# schematic.net
KiCad netlist of a schematic drawn in EAGLE
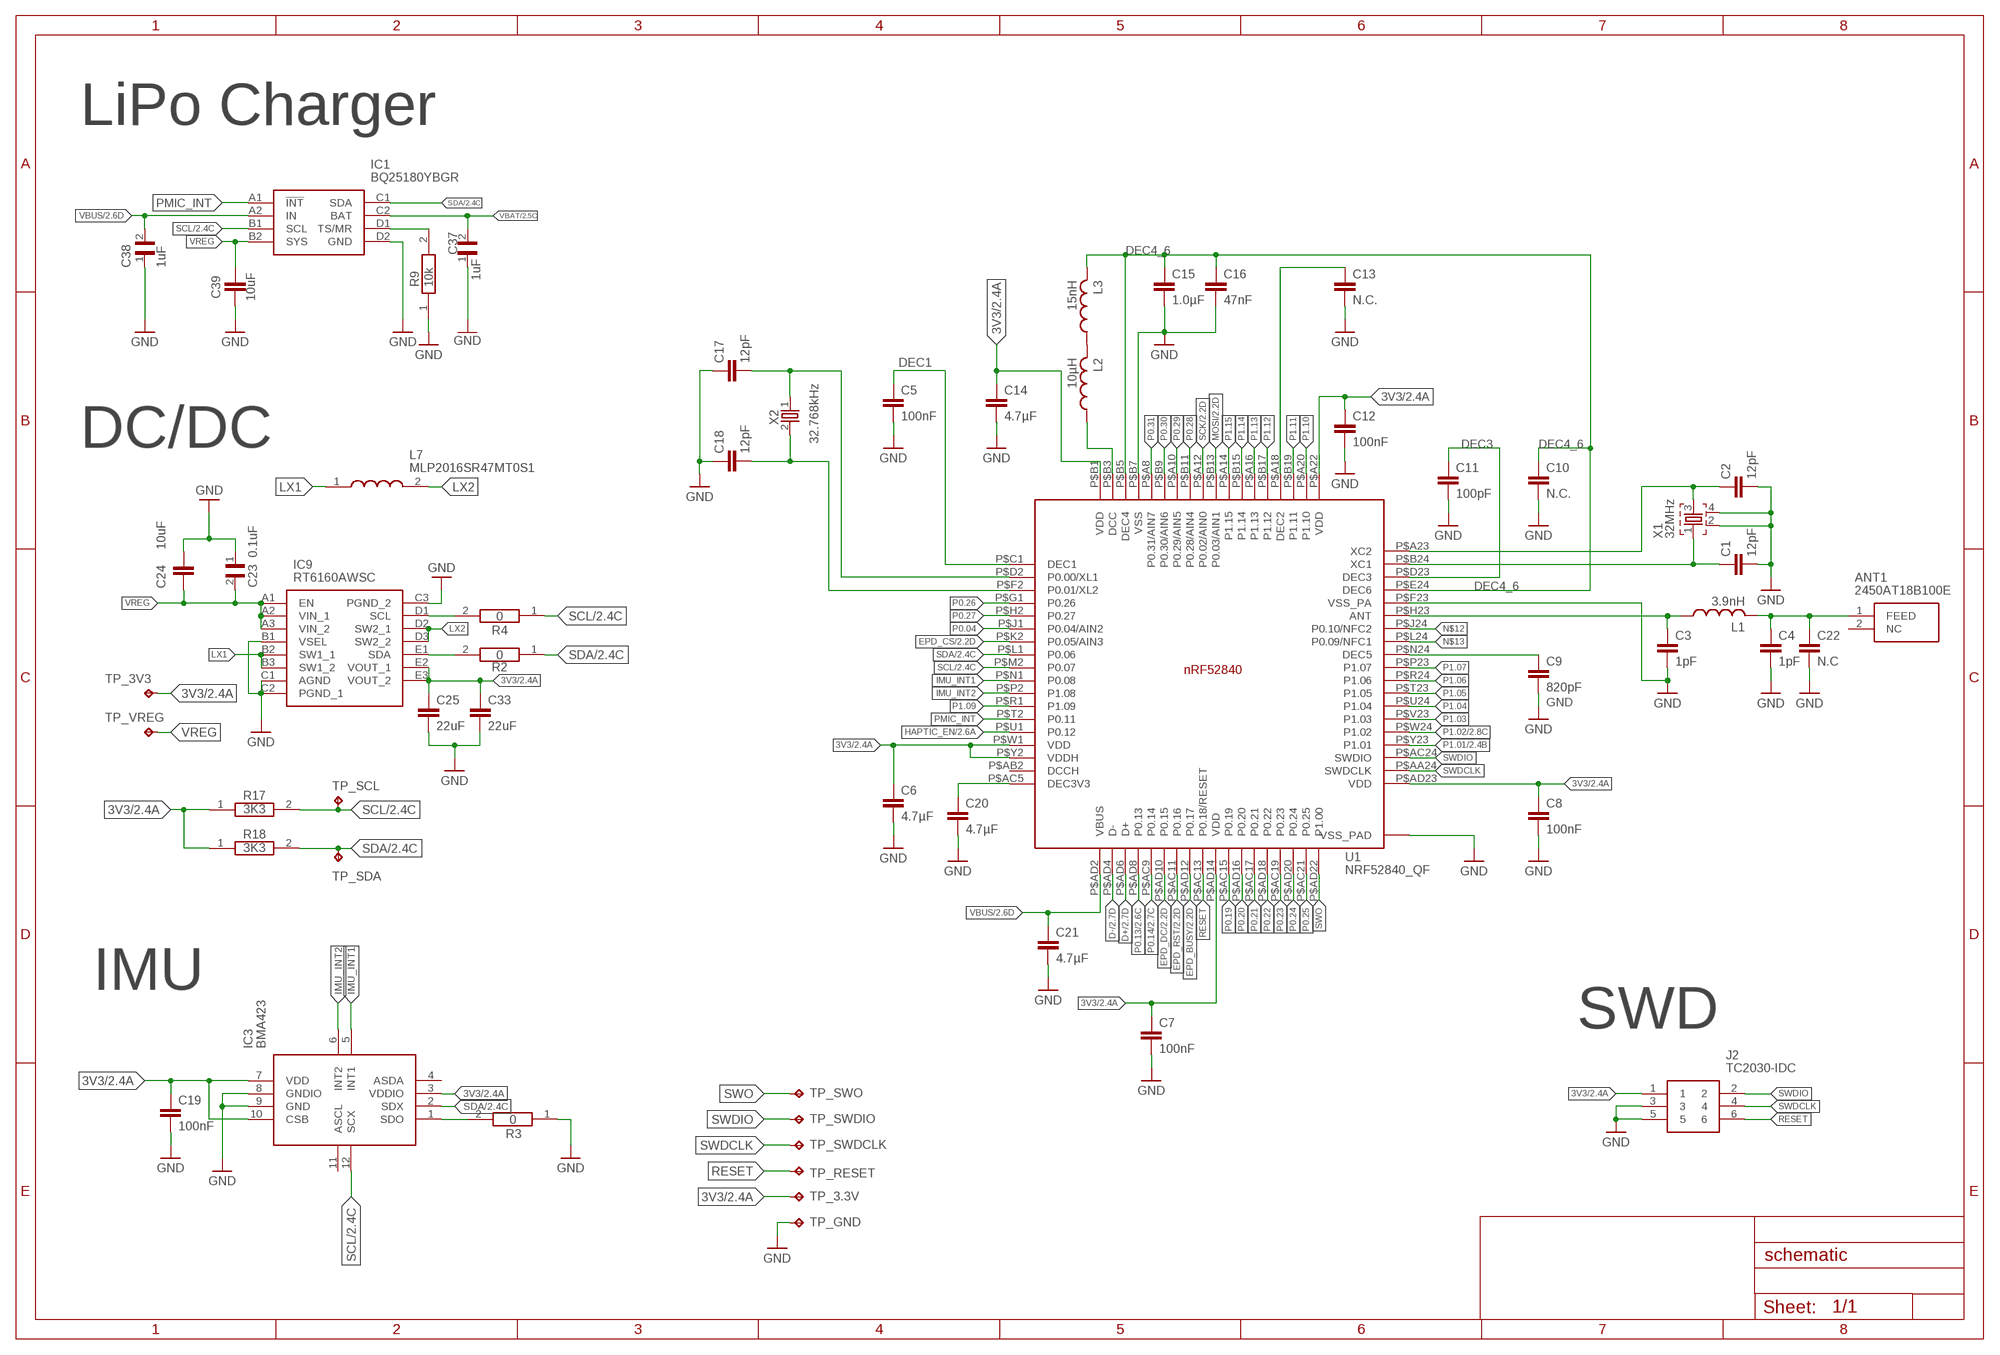
[diagram p0: schematic, sheet 1, part 1 of 2]
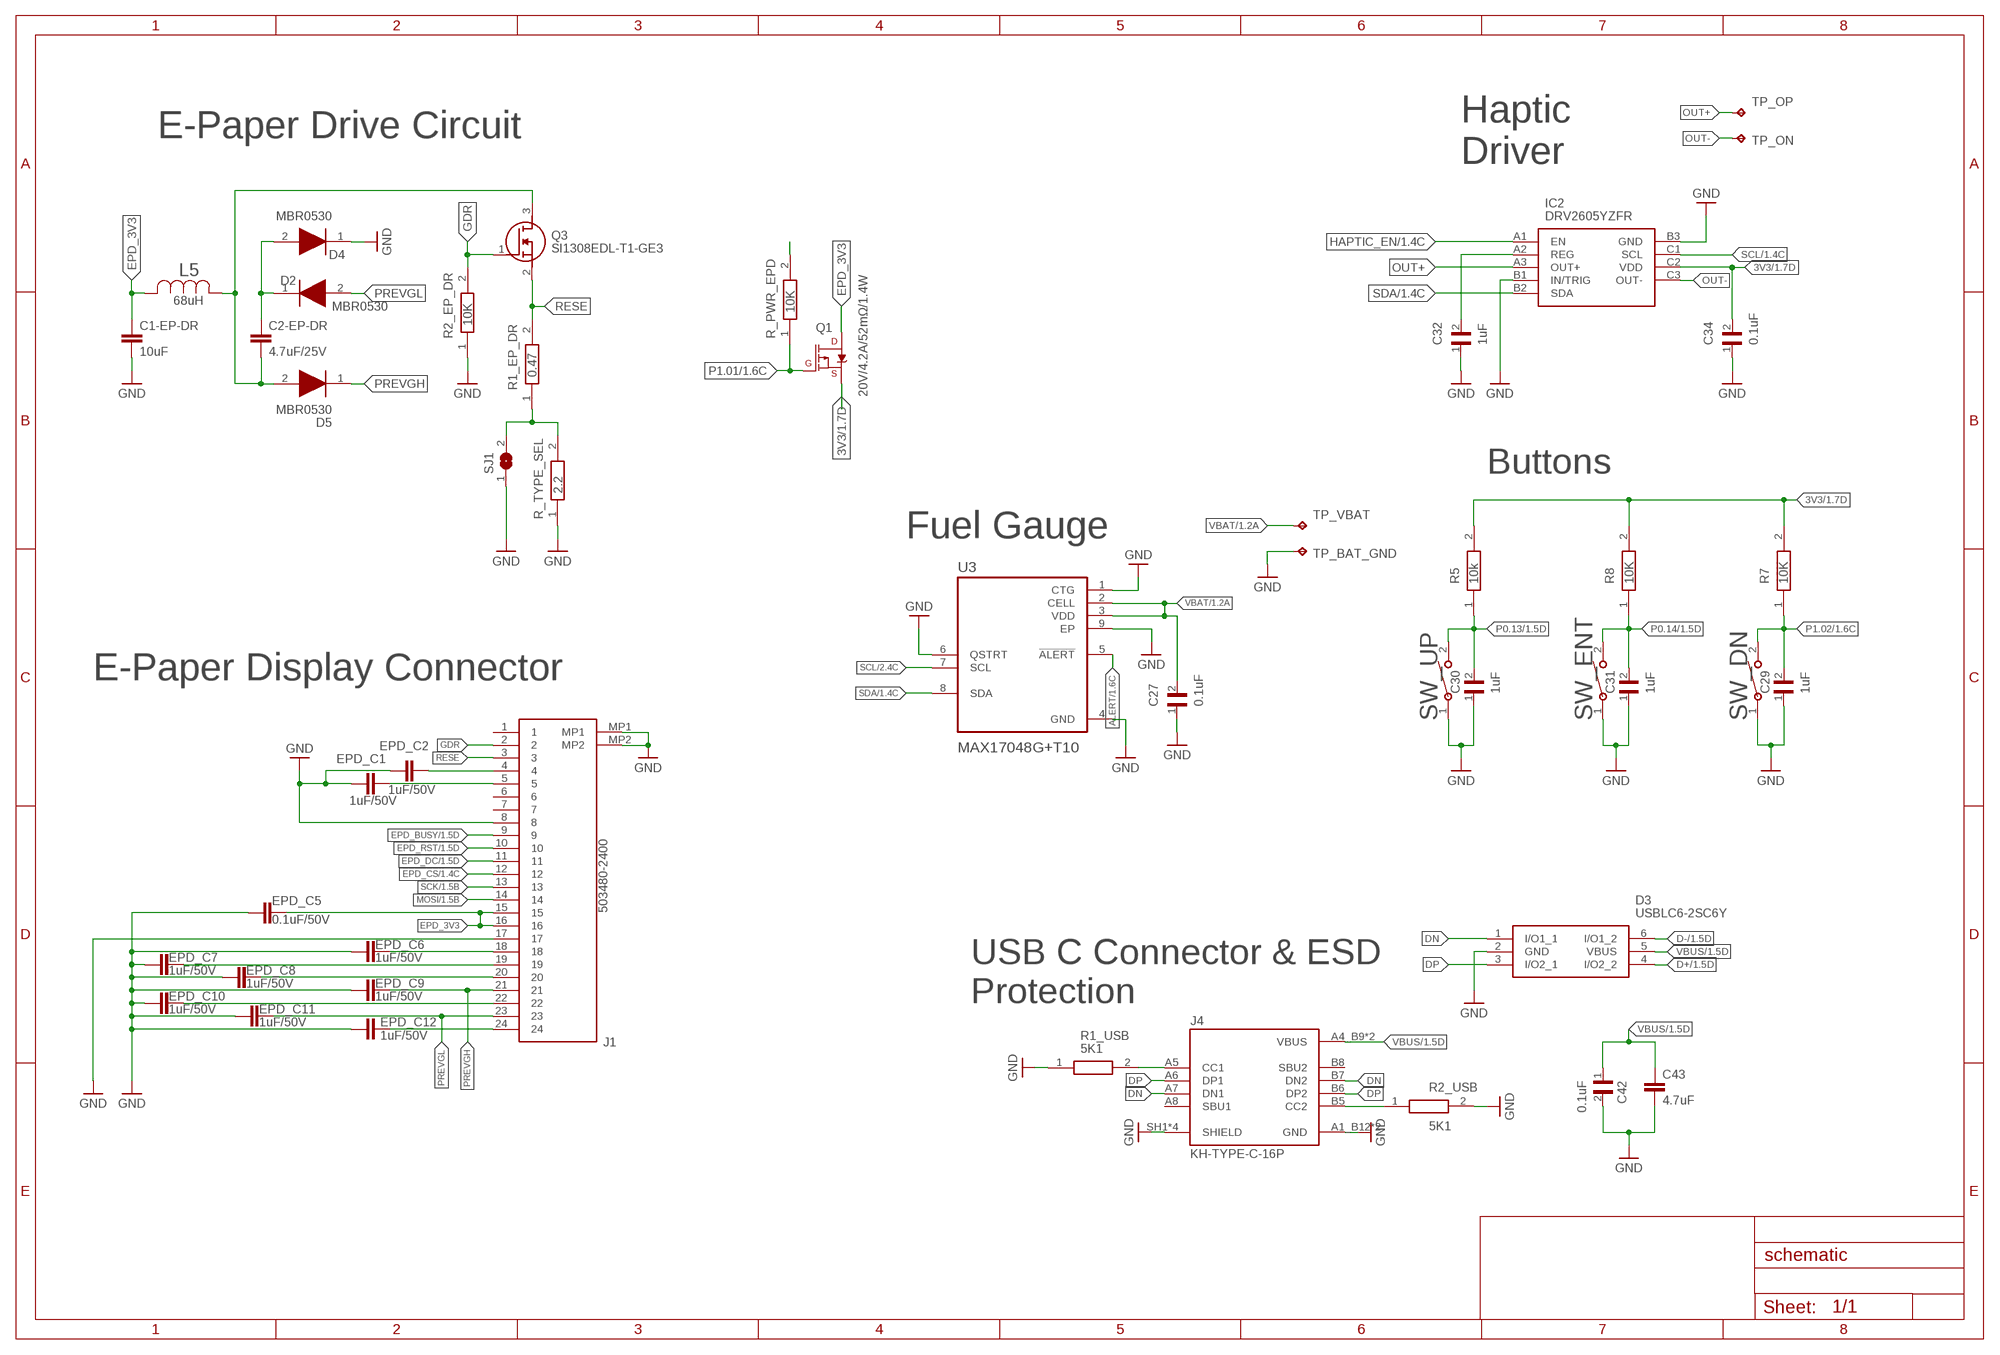
[diagram p1: schematic, sheet 1, part 2 of 2]

(export (version "E")
  (design (tool "Eeschema 10.0.6"))
  (components
    (comp (ref "ANT1")
      (value "2450AT18B100E")
      (footprint "eagle-import:2450AT18B100E_ANTC3216X140N")
      (fields (field (name "MOUSER_PART_NUMBER") "609-2450AT18B100E"))
      (libsource (lib "eagle-import") (part "2450AT18B100E_2450AT18B100E"))
    )
    (comp (ref "C1")
      (value "12pF")
      (footprint "eagle-import:NORDIC_NRF_3_RESC0201_L")
      (libsource (lib "eagle-import") (part "NORDIC_NRF_3_CAPACITOR_0201_L"))
    )
    (comp (ref "C1-EP-DR")
      (value "10uF")
      (footprint "eagle-import:PERFECT_0402_0402")
      (libsource (lib "eagle-import") (part "PERFECT_0402_CAP_0402"))
    )
    (comp (ref "C2")
      (value "12pF")
      (footprint "eagle-import:NORDIC_NRF_3_RESC0201_L")
      (libsource (lib "eagle-import") (part "NORDIC_NRF_3_CAPACITOR_0201_L"))
    )
    (comp (ref "C2-EP-DR")
      (value "4.7uF/25V")
      (footprint "eagle-import:PERFECT_0402_0402")
      (libsource (lib "eagle-import") (part "PERFECT_0402_CAP_0402"))
    )
    (comp (ref "C3")
      (value "1pF")
      (footprint "eagle-import:NORDIC_NRF_3_RESC0201_L")
      (libsource (lib "eagle-import") (part "NORDIC_NRF_3_CAPACITOR_0201_L"))
    )
    (comp (ref "C4")
      (value "1pF")
      (footprint "eagle-import:NORDIC_NRF_3_RESC0201_L")
      (libsource (lib "eagle-import") (part "NORDIC_NRF_3_CAPACITOR_0201_L"))
    )
    (comp (ref "C5")
      (value "100nF")
      (footprint "eagle-import:NORDIC_NRF_3_RESC0201_L")
      (libsource (lib "eagle-import") (part "NORDIC_NRF_3_CAPACITOR_0201_L"))
    )
    (comp (ref "C6")
      (value "4.7µF")
      (footprint "eagle-import:PERFECT_0402_0402")
      (libsource (lib "eagle-import") (part "PERFECT_0402_CAP_0402"))
    )
    (comp (ref "C7")
      (value "100nF")
      (footprint "eagle-import:NORDIC_NRF_3_RESC0201_L")
      (libsource (lib "eagle-import") (part "NORDIC_NRF_3_CAPACITOR_0201_L"))
    )
    (comp (ref "C8")
      (value "100nF")
      (footprint "eagle-import:NORDIC_NRF_3_RESC0201_L")
      (libsource (lib "eagle-import") (part "NORDIC_NRF_3_CAPACITOR_0201_L"))
    )
    (comp (ref "C9")
      (value "820pF")
      (footprint "eagle-import:NORDIC_NRF_3_RESC0201_L")
      (libsource (lib "eagle-import") (part "NORDIC_NRF_3_CAPACITOR_0201_L"))
    )
    (comp (ref "C10")
      (value "N.C.")
      (footprint "eagle-import:NORDIC_NRF_3_RESC0201_L")
      (libsource (lib "eagle-import") (part "NORDIC_NRF_3_CAPACITOR_0201_L"))
    )
    (comp (ref "C11")
      (value "100pF")
      (footprint "eagle-import:NORDIC_NRF_3_RESC0201_L")
      (libsource (lib "eagle-import") (part "NORDIC_NRF_3_CAPACITOR_0201_L"))
    )
    (comp (ref "C12")
      (value "100nF")
      (footprint "eagle-import:NORDIC_NRF_3_RESC0201_L")
      (libsource (lib "eagle-import") (part "NORDIC_NRF_3_CAPACITOR_0201_L"))
    )
    (comp (ref "C13")
      (value "N.C.")
      (footprint "eagle-import:NORDIC_NRF_3_RESC0201_L")
      (libsource (lib "eagle-import") (part "NORDIC_NRF_3_CAPACITOR_0201_L"))
    )
    (comp (ref "C14")
      (value "4.7µF")
      (footprint "eagle-import:PERFECT_0402_0402")
      (libsource (lib "eagle-import") (part "PERFECT_0402_CAP_0402"))
    )
    (comp (ref "C15")
      (value "1.0µF")
      (footprint "eagle-import:PERFECT_0402_0402")
      (libsource (lib "eagle-import") (part "PERFECT_0402_CAP_0402"))
    )
    (comp (ref "C16")
      (value "47nF")
      (footprint "eagle-import:NORDIC_NRF_3_RESC0201_L")
      (libsource (lib "eagle-import") (part "NORDIC_NRF_3_CAPACITOR_0201_L"))
    )
    (comp (ref "C17")
      (value "12pF")
      (footprint "eagle-import:NORDIC_NRF_3_RESC0201_L")
      (libsource (lib "eagle-import") (part "NORDIC_NRF_3_CAPACITOR_0201_L"))
    )
    (comp (ref "C18")
      (value "12pF")
      (footprint "eagle-import:NORDIC_NRF_3_RESC0201_L")
      (libsource (lib "eagle-import") (part "NORDIC_NRF_3_CAPACITOR_0201_L"))
    )
    (comp (ref "C19")
      (value "100nF")
      (footprint "eagle-import:NORDIC_NRF_3_RESC0201_L")
      (libsource (lib "eagle-import") (part "NORDIC_NRF_3_CAPACITOR_0201_L"))
    )
    (comp (ref "C20")
      (value "4.7µF")
      (footprint "eagle-import:PERFECT_0402_0402")
      (libsource (lib "eagle-import") (part "PERFECT_0402_CAP_0402"))
    )
    (comp (ref "C21")
      (value "4.7µF")
      (footprint "eagle-import:PERFECT_0402_0402")
      (libsource (lib "eagle-import") (part "PERFECT_0402_CAP_0402"))
    )
    (comp (ref "C22")
      (value "N.C")
      (footprint "eagle-import:NORDIC_NRF_3_RESC0201_L")
      (libsource (lib "eagle-import") (part "NORDIC_NRF_3_CAPACITOR_0201_L"))
    )
    (comp (ref "C23")
      (value "0.1uF")
      (footprint "eagle-import:ERA-1AEB3401C_0201")
      (libsource (lib "eagle-import") (part "GRM011R60J152KE01L_1_GRM011R60J152KE01L"))
    )
    (comp (ref "C24")
      (value "10uF")
      (footprint "eagle-import:PERFECT_0402_0402")
      (libsource (lib "eagle-import") (part "PERFECT_0402_CAP_0402"))
    )
    (comp (ref "C25")
      (value "22uF")
      (footprint "eagle-import:PERFECT_0402_0402")
      (libsource (lib "eagle-import") (part "PERFECT_0402_CAP_0402"))
    )
    (comp (ref "C27")
      (value "0.1uF")
      (footprint "eagle-import:ERA-1AEB3401C_0201")
      (libsource (lib "eagle-import") (part "GRM011R60J152KE01L_1_GRM011R60J152KE01L"))
    )
    (comp (ref "C29")
      (value "1uF")
      (footprint "eagle-import:ERA-1AEB3401C_0201")
      (libsource (lib "eagle-import") (part "GRM011R60J152KE01L_1_GRM011R60J152KE01L"))
    )
    (comp (ref "C30")
      (value "1uF")
      (footprint "eagle-import:ERA-1AEB3401C_0201")
      (libsource (lib "eagle-import") (part "GRM011R60J152KE01L_1_GRM011R60J152KE01L"))
    )
    (comp (ref "C31")
      (value "1uF")
      (footprint "eagle-import:ERA-1AEB3401C_0201")
      (libsource (lib "eagle-import") (part "GRM011R60J152KE01L_1_GRM011R60J152KE01L"))
    )
    (comp (ref "C32")
      (value "1uF")
      (footprint "eagle-import:ERA-1AEB3401C_0201")
      (libsource (lib "eagle-import") (part "GRM011R60J152KE01L_1_GRM011R60J152KE01L"))
    )
    (comp (ref "C33")
      (value "22uF")
      (footprint "eagle-import:PERFECT_0402_0402")
      (libsource (lib "eagle-import") (part "PERFECT_0402_CAP_0402"))
    )
    (comp (ref "C34")
      (value "0.1uF")
      (footprint "eagle-import:ERA-1AEB3401C_0201")
      (libsource (lib "eagle-import") (part "GRM011R60J152KE01L_1_GRM011R60J152KE01L"))
    )
    (comp (ref "C37")
      (value "1uF")
      (footprint "eagle-import:ERA-1AEB3401C_0201")
      (libsource (lib "eagle-import") (part "GRM011R60J152KE01L_1_GRM011R60J152KE01L"))
    )
    (comp (ref "C38")
      (value "1uF")
      (footprint "eagle-import:ERA-1AEB3401C_0201")
      (libsource (lib "eagle-import") (part "GRM011R60J152KE01L_1_GRM011R60J152KE01L"))
    )
    (comp (ref "C39")
      (value "10uF")
      (footprint "eagle-import:PERFECT_0402_0402")
      (libsource (lib "eagle-import") (part "PERFECT_0402_CAP_0402"))
    )
    (comp (ref "C42")
      (value "0.1uF")
      (footprint "eagle-import:ERA-1AEB3401C_0201")
      (libsource (lib "eagle-import") (part "GRM011R60J152KE01L_1_GRM011R60J152KE01L"))
    )
    (comp (ref "C43")
      (value "4.7uF")
      (footprint "eagle-import:PERFECT_0402_0402")
      (libsource (lib "eagle-import") (part "PERFECT_0402_CAP_0402"))
    )
    (comp (ref "D2")
      (value "MBR0530")
      (footprint "eagle-import:ESP32_C6_LIBRARY_5_SOD3716X135N")
      (fields (field (name "MF") "ON Semiconductor"))
      (libsource (lib "eagle-import") (part "ESP32_C6_LIBRARY_5_MBR0530"))
    )
    (comp (ref "D3")
      (value "USBLC6-2SC6Y")
      (footprint "eagle-import:ESP32_C6_LIBRARY_3_SOT95P280X145-6N")
      (fields (field (name "MF") "STMicroelectronics"))
      (libsource (lib "eagle-import") (part "ESP32_C6_LIBRARY_3_USBLC6-2SC6Y"))
    )
    (comp (ref "D4")
      (value "MBR0530")
      (footprint "eagle-import:ESP32_C6_LIBRARY_5_SOD3716X135N")
      (fields (field (name "MF") "ON Semiconductor"))
      (libsource (lib "eagle-import") (part "ESP32_C6_LIBRARY_5_MBR0530"))
    )
    (comp (ref "D5")
      (value "MBR0530")
      (footprint "eagle-import:ESP32_C6_LIBRARY_5_SOD3716X135N")
      (fields (field (name "MF") "ON Semiconductor"))
      (libsource (lib "eagle-import") (part "ESP32_C6_LIBRARY_5_MBR0530"))
    )
    (comp (ref "EPD_C1")
      (value "1uF/50V")
      (footprint "eagle-import:PERFECT_0402_0402")
      (libsource (lib "eagle-import") (part "PERFECT_0402_CAP_0402"))
    )
    (comp (ref "EPD_C2")
      (value "1uF/50V")
      (footprint "eagle-import:PERFECT_0402_0402")
      (libsource (lib "eagle-import") (part "PERFECT_0402_CAP_0402"))
    )
    (comp (ref "EPD_C5")
      (value "0.1uF/50V")
      (footprint "eagle-import:NORDIC_NRF_3_RESC0201_L")
      (libsource (lib "eagle-import") (part "NORDIC_NRF_3_CAPACITOR_0201_L"))
    )
    (comp (ref "EPD_C6")
      (value "1uF/50V")
      (footprint "eagle-import:PERFECT_0402_0402")
      (libsource (lib "eagle-import") (part "PERFECT_0402_CAP_0402"))
    )
    (comp (ref "EPD_C7")
      (value "1uF/50V")
      (footprint "eagle-import:PERFECT_0402_0402")
      (libsource (lib "eagle-import") (part "PERFECT_0402_CAP_0402"))
    )
    (comp (ref "EPD_C8")
      (value "1uF/50V")
      (footprint "eagle-import:PERFECT_0402_0402")
      (libsource (lib "eagle-import") (part "PERFECT_0402_CAP_0402"))
    )
    (comp (ref "EPD_C9")
      (value "1uF/50V")
      (footprint "eagle-import:PERFECT_0402_0402")
      (libsource (lib "eagle-import") (part "PERFECT_0402_CAP_0402"))
    )
    (comp (ref "EPD_C10")
      (value "1uF/50V")
      (footprint "eagle-import:PERFECT_0402_0402")
      (libsource (lib "eagle-import") (part "PERFECT_0402_CAP_0402"))
    )
    (comp (ref "EPD_C11")
      (value "1uF/50V")
      (footprint "eagle-import:PERFECT_0402_0402")
      (libsource (lib "eagle-import") (part "PERFECT_0402_CAP_0402"))
    )
    (comp (ref "EPD_C12")
      (value "1uF/50V")
      (footprint "eagle-import:PERFECT_0402_0402")
      (libsource (lib "eagle-import") (part "PERFECT_0402_CAP_0402"))
    )
    (comp (ref "IC1")
      (value "BQ25180YBGR")
      (footprint "eagle-import:BQ25180YBGR_BGA8C40P2X4_100X155X50")
      (fields (field (name "MOUSER_PART_NUMBER") "595-BQ25180YBGR"))
      (libsource (lib "eagle-import") (part "BQ25180YBGR_BQ25180YBGR"))
    )
    (comp (ref "IC2")
      (value "DRV2605YZFR")
      (footprint "eagle-import:DRV2605YZFR_BGA9C50P3X3_144X144X62")
      (libsource (lib "eagle-import") (part "DRV2605YZFR_DRV2605YZFR"))
    )
    (comp (ref "IC3")
      (value "BMA423")
      (footprint "eagle-import:BMA423_BMA423")
      (fields (field (name "MOUSER_PART_NUMBER") "262-BMA423"))
      (libsource (lib "eagle-import") (part "BMA423_BMA423"))
    )
    (comp (ref "IC9")
      (value "RT6160AWSC")
      (footprint "eagle-import:RT6160AWSC_BGA15C40P3X5_140X230X60")
      (fields (field (name "MOUSER_PART_NUMBER") "835-RT6160AWSC"))
      (libsource (lib "eagle-import") (part "RT6160AWSC_RT6160AWSC"))
    )
    (comp (ref "J1")
      (value "503480-2400")
      (footprint "eagle-import:503480-2400_5034802400")
      (fields (field (name "MOUSER_PART_NUMBER") "538-503480-2400"))
      (libsource (lib "eagle-import") (part "503480-2400_503480-2400"))
    )
    (comp (ref "J2")
      (value "TC2030-IDC")
      (footprint "eagle-import:TC2030-IDC_TC2030IDC")
      (libsource (lib "eagle-import") (part "TC2030-IDC_TC2030-IDC"))
    )
    (comp (ref "J4")
      (value "KH-TYPE-C-16P")
      (footprint "eagle-import:KH-TYPE-C-16P_KINGHELM_KH-TYPE-C-16P")
      (fields (field (name "MF") "kinghelm"))
      (libsource (lib "eagle-import") (part "KH-TYPE-C-16P_KH-TYPE-C-16P"))
    )
    (comp (ref "L1")
      (value "3.9nH")
      (footprint "eagle-import:NORDIC_NRF_2_RESC0402_N")
      (libsource (lib "eagle-import") (part "NORDIC_NRF_2_INDUCTOR_0402_L"))
    )
    (comp (ref "L2")
      (value "10µH")
      (footprint "eagle-import:NORDIC_NRF_2_RESC0402_N")
      (libsource (lib "eagle-import") (part "NORDIC_NRF_2_INDUCTOR_0402_L"))
    )
    (comp (ref "L3")
      (value "15nH")
      (footprint "eagle-import:NORDIC_NRF_2_RESC0402_N")
      (libsource (lib "eagle-import") (part "NORDIC_NRF_2_INDUCTOR_0402_L"))
    )
    (comp (ref "L5")
      (value "68uH")
      (footprint "eagle-import:ESP32_C6_LIBRARY_2_IND_4828-WE-TPC_WRE")
      (fields
        (field (name "MANUFACTURER_PART_NUMBER") "744043680")
        (field (name "COPYRIGHT") "Copyright (C) 2024 Ultra Librarian. All rights reserved.")
      )
      (libsource (lib "eagle-import") (part "ESP32_C6_LIBRARY_2_744043680IND_4828-WE-TPC_WRE"))
    )
    (comp (ref "L7")
      (value "MLP2016SR47MT0S1")
      (footprint "eagle-import:MLP2016SR47MT0S1_INDC2016X100N")
      (fields (field (name "MANUFACTURER_PART_NUMBER") "FTC252012SR47MBCA"))
      (libsource (lib "eagle-import") (part "MLP2016SR47MT0S1_FTC252012SR47MBCA"))
    )
    (comp (ref "Q1")
      (value "20V/4.2A/52mΩ/1.4W")
      (footprint "eagle-import:ESP32_C6_LIBRARY_4_ESP32_C6_LIBRARY_4_ESP32_C6_LIBRARY_4_ESP32_C6_LIBRARY_4_ESP32_WROVER_SPARKFUN-DISCRETESEMI_SOT23-3")
      (libsource (lib "eagle-import") (part "ESP32_C6_LIBRARY_4_ESP32_WROVER_SPARKFUN-DISCRETESEMI_MOSFET_PCH-DMG2305UX-7"))
    )
    (comp (ref "Q3")
      (value "SI1308EDL-T1-GE3")
      (footprint "eagle-import:ESP32_C6_LIBRARY_6_SOT65P210X110-3N")
      (fields (field (name "MF") "Vishay Siliconix"))
      (libsource (lib "eagle-import") (part "ESP32_C6_LIBRARY_6_SI1308EDL-T1-GE3"))
    )
    (comp (ref "R1_EP_DR")
      (value "0.47")
      (footprint "eagle-import:CPF0201D7K68C1_0201")
      (libsource (lib "eagle-import") (part "CPF0201D7K68C1_CPF0201D7K68C1"))
    )
    (comp (ref "R1_USB")
      (value "5K1")
      (footprint "eagle-import:CPF0201D7K68C1_0201")
      (libsource (lib "eagle-import") (part "CPF0201D7K68C1_CPF0201D7K68C1"))
    )
    (comp (ref "R2")
      (value "0")
      (footprint "eagle-import:ERA-1AEB3401C_0201")
      (libsource (lib "eagle-import") (part "ERA-1AEB3401C_CPF0201D7K68C1"))
    )
    (comp (ref "R2_EP_DR")
      (value "10K")
      (footprint "eagle-import:CPF0201D7K68C1_0201")
      (libsource (lib "eagle-import") (part "CPF0201D7K68C1_CPF0201D7K68C1"))
    )
    (comp (ref "R2_USB")
      (value "5K1")
      (footprint "eagle-import:CPF0201D7K68C1_0201")
      (libsource (lib "eagle-import") (part "CPF0201D7K68C1_CPF0201D7K68C1"))
    )
    (comp (ref "R3")
      (value "0")
      (footprint "eagle-import:CPF0201D7K68C1_0201")
      (libsource (lib "eagle-import") (part "CPF0201D7K68C1_CPF0201D7K68C1"))
    )
    (comp (ref "R4")
      (value "0")
      (footprint "eagle-import:ERA-1AEB3401C_0201")
      (libsource (lib "eagle-import") (part "ERA-1AEB3401C_CPF0201D7K68C1"))
    )
    (comp (ref "R5")
      (value "10k")
      (footprint "eagle-import:CPF0201D7K68C1_0201")
      (libsource (lib "eagle-import") (part "CPF0201D7K68C1_CPF0201D7K68C1"))
    )
    (comp (ref "R7")
      (value "10K")
      (footprint "eagle-import:CPF0201D7K68C1_0201")
      (libsource (lib "eagle-import") (part "CPF0201D7K68C1_CPF0201D7K68C1"))
    )
    (comp (ref "R8")
      (value "10K")
      (footprint "eagle-import:CPF0201D7K68C1_0201")
      (libsource (lib "eagle-import") (part "CPF0201D7K68C1_CPF0201D7K68C1"))
    )
    (comp (ref "R9")
      (value "10k")
      (footprint "eagle-import:ERA-1AEB3401C_0201")
      (libsource (lib "eagle-import") (part "ERA-1AEB3401C_CPF0201D7K68C1"))
    )
    (comp (ref "R17")
      (value "3K3")
      (footprint "eagle-import:ERA-1AEB3401C_0201")
      (libsource (lib "eagle-import") (part "ERA-1AEB3401C_CPF0201D7K68C1"))
    )
    (comp (ref "R18")
      (value "3K3")
      (footprint "eagle-import:ERA-1AEB3401C_0201")
      (libsource (lib "eagle-import") (part "ERA-1AEB3401C_CPF0201D7K68C1"))
    )
    (comp (ref "R_PWR_EPD")
      (value "10K")
      (footprint "eagle-import:CPF0201D7K68C1_0201")
      (libsource (lib "eagle-import") (part "CPF0201D7K68C1_CPF0201D7K68C1"))
    )
    (comp (ref "R_TYPE_SEL")
      (value "2.2")
      (footprint "eagle-import:CPF0201D7K68C1_0201")
      (libsource (lib "eagle-import") (part "CPF0201D7K68C1_CPF0201D7K68C1"))
    )
    (comp (ref "SJ1")
      (value "ESP32_C6_LIBRARY_7_JUMPER_SJ")
      (footprint "eagle-import:ESP32_C6_LIBRARY_7_JUMPER_SJ")
      (libsource (lib "eagle-import") (part "ESP32_C6_LIBRARY_7_JUMPER_SJ"))
    )
    (comp (ref "SW_DN")
      (value "2025-10-22_07-23-44_LIBRARY_EVP-AKE31ASW_EVP-AKE31A_PAN")
      (footprint "eagle-import:2025-10-22_07-23-44_LIBRARY_SW_EVP-AKE31A_PAN")
      (fields
        (field (name "MANUFACTURER_PART_NUMBER") "EVP-AKE31A")
        (field (name "COPYRIGHT") "Copyright (C) 2025 Ultra Librarian. All rights reserved.")
      )
      (libsource (lib "eagle-import") (part "2025-10-22_07-23-44_LIBRARY_EVP-AKE31ASW_EVP-AKE31A_PAN"))
    )
    (comp (ref "SW_ENT")
      (value "2025-10-22_07-23-44_LIBRARY_EVP-AKE31ASW_EVP-AKE31A_PAN")
      (footprint "eagle-import:2025-10-22_07-23-44_LIBRARY_SW_EVP-AKE31A_PAN")
      (fields
        (field (name "MANUFACTURER_PART_NUMBER") "EVP-AKE31A")
        (field (name "COPYRIGHT") "Copyright (C) 2025 Ultra Librarian. All rights reserved.")
      )
      (libsource (lib "eagle-import") (part "2025-10-22_07-23-44_LIBRARY_EVP-AKE31ASW_EVP-AKE31A_PAN"))
    )
    (comp (ref "SW_UP")
      (value "2025-10-22_07-23-44_LIBRARY_EVP-AKE31ASW_EVP-AKE31A_PAN")
      (footprint "eagle-import:2025-10-22_07-23-44_LIBRARY_SW_EVP-AKE31A_PAN")
      (fields
        (field (name "MANUFACTURER_PART_NUMBER") "EVP-AKE31A")
        (field (name "COPYRIGHT") "Copyright (C) 2025 Ultra Librarian. All rights reserved.")
      )
      (libsource (lib "eagle-import") (part "2025-10-22_07-23-44_LIBRARY_EVP-AKE31ASW_EVP-AKE31A_PAN"))
    )
    (comp (ref "TP_3.3V")
      (value "HECTOR_WATCH_1_TPTP20R")
      (footprint "eagle-import:HECTOR_WATCH_1_TP20R")
      (libsource (lib "eagle-import") (part "HECTOR_WATCH_1_TPTP20R"))
    )
    (comp (ref "TP_3V3")
      (value "HECTOR_WATCH_1_TPTP20R")
      (footprint "eagle-import:HECTOR_WATCH_1_TP20R")
      (libsource (lib "eagle-import") (part "HECTOR_WATCH_1_TPTP20R"))
    )
    (comp (ref "TP_BAT_GND")
      (value "HECTOR_WATCH_1_TPTP20R")
      (footprint "eagle-import:HECTOR_WATCH_1_TP20R")
      (libsource (lib "eagle-import") (part "HECTOR_WATCH_1_TPTP20R"))
    )
    (comp (ref "TP_GND")
      (value "HECTOR_WATCH_1_TPTP20R")
      (footprint "eagle-import:HECTOR_WATCH_1_TP20R")
      (libsource (lib "eagle-import") (part "HECTOR_WATCH_1_TPTP20R"))
    )
    (comp (ref "TP_ON")
      (value "HECTOR_WATCH_1_TPTP20R")
      (footprint "eagle-import:HECTOR_WATCH_1_TP20R")
      (libsource (lib "eagle-import") (part "HECTOR_WATCH_1_TPTP20R"))
    )
    (comp (ref "TP_OP")
      (value "HECTOR_WATCH_1_TPTP20R")
      (footprint "eagle-import:HECTOR_WATCH_1_TP20R")
      (libsource (lib "eagle-import") (part "HECTOR_WATCH_1_TPTP20R"))
    )
    (comp (ref "TP_RESET")
      (value "HECTOR_WATCH_1_TPTP20R")
      (footprint "eagle-import:HECTOR_WATCH_1_TP20R")
      (libsource (lib "eagle-import") (part "HECTOR_WATCH_1_TPTP20R"))
    )
    (comp (ref "TP_SCL")
      (value "HECTOR_WATCH_1_TPTP20R")
      (footprint "eagle-import:HECTOR_WATCH_1_TP20R")
      (libsource (lib "eagle-import") (part "HECTOR_WATCH_1_TPTP20R"))
    )
    (comp (ref "TP_SDA")
      (value "HECTOR_WATCH_1_TPTP20R")
      (footprint "eagle-import:HECTOR_WATCH_1_TP20R")
      (libsource (lib "eagle-import") (part "HECTOR_WATCH_1_TPTP20R"))
    )
    (comp (ref "TP_SWDCLK")
      (value "HECTOR_WATCH_1_TPTP20R")
      (footprint "eagle-import:HECTOR_WATCH_1_TP20R")
      (libsource (lib "eagle-import") (part "HECTOR_WATCH_1_TPTP20R"))
    )
    (comp (ref "TP_SWDIO")
      (value "HECTOR_WATCH_1_TPTP20R")
      (footprint "eagle-import:HECTOR_WATCH_1_TP20R")
      (libsource (lib "eagle-import") (part "HECTOR_WATCH_1_TPTP20R"))
    )
    (comp (ref "TP_SWO")
      (value "HECTOR_WATCH_1_TPTP20R")
      (footprint "eagle-import:HECTOR_WATCH_1_TP20R")
      (libsource (lib "eagle-import") (part "HECTOR_WATCH_1_TPTP20R"))
    )
    (comp (ref "TP_VBAT")
      (value "HECTOR_WATCH_1_TPTP20R")
      (footprint "eagle-import:HECTOR_WATCH_1_TP20R")
      (libsource (lib "eagle-import") (part "HECTOR_WATCH_1_TPTP20R"))
    )
    (comp (ref "TP_VREG")
      (value "HECTOR_WATCH_1_TPTP20R")
      (footprint "eagle-import:HECTOR_WATCH_1_TP20R")
      (libsource (lib "eagle-import") (part "HECTOR_WATCH_1_TPTP20R"))
    )
    (comp (ref "U1")
      (value "NRF52840_QF")
      (footprint "eagle-import:NORDIC_NRF_4_AQFN50P700X700X85_HS-74N")
      (libsource (lib "eagle-import") (part "NORDIC_NRF_4_NRF52840_QF"))
    )
    (comp (ref "U3")
      (value "MAX17048G+T10")
      (footprint "eagle-import:ESP32_C6_LIBRARY_SON50P200X200X80-9N")
      (fields (field (name "MF") "Analog Devices"))
      (libsource (lib "eagle-import") (part "ESP32_C6_LIBRARY_MAX17048G+T10"))
    )
    (comp (ref "X1")
      (value "32MHz")
      (footprint "eagle-import:NORDIC_NRF_BT-XTAL_2016_N")
      (libsource (lib "eagle-import") (part "NORDIC_NRF_XTAL_32MHZ"))
    )
    (comp (ref "X2")
      (value "32.768kHz")
      (footprint "eagle-import:NORDIC_NRF_1_XTAL_3215_N")
      (libsource (lib "eagle-import") (part "NORDIC_NRF_1_XTAL_32KHZ"))
    )
  )
  (nets
    (net (code "1") (name "/DEC1") (class "Default")
      (node (ref "C5") (pin "1") (pinfunction "1_1") (pintype "passive"))
      (node (ref "U1") (pin "P$C1") (pinfunction "DEC1_P$C1") (pintype "power_in"))
    )
    (net (code "2") (name "/DEC3") (class "Default")
      (node (ref "C11") (pin "1") (pinfunction "1_1") (pintype "passive"))
      (node (ref "U1") (pin "P$D23") (pinfunction "DEC3_P$D23") (pintype "bidirectional"))
    )
    (net (code "3") (name "/DEC4_6") (class "Default")
      (node (ref "C10") (pin "1") (pinfunction "1_1") (pintype "passive"))
      (node (ref "C15") (pin "1") (pinfunction "1_1") (pintype "passive"))
      (node (ref "C16") (pin "1") (pinfunction "1_1") (pintype "passive"))
      (node (ref "L3") (pin "2") (pinfunction "2_2") (pintype "passive"))
      (node (ref "U1") (pin "P$B5") (pinfunction "DEC4_P$B5") (pintype "power_in"))
      (node (ref "U1") (pin "P$E24") (pinfunction "DEC6_P$E24") (pintype "bidirectional"))
    )
    (net (code "4") (name "3V3{slash}1.7D") (class "Default")
      (node (ref "C34") (pin "2") (pinfunction "2_2") (pintype "passive"))
      (node (ref "IC2") (pin "C2") (pinfunction "VDD_C2") (pintype "bidirectional"))
      (node (ref "Q1") (pin "2") (pinfunction "S_2") (pintype "bidirectional"))
      (node (ref "R5") (pin "2") (pinfunction "2_2") (pintype "bidirectional"))
      (node (ref "R7") (pin "2") (pinfunction "2_2") (pintype "bidirectional"))
      (node (ref "R8") (pin "2") (pinfunction "2_2") (pintype "bidirectional"))
    )
    (net (code "5") (name "3V3{slash}2.4A") (class "Default")
      (node (ref "C12") (pin "1") (pinfunction "1_1") (pintype "passive"))
      (node (ref "C14") (pin "1") (pinfunction "1_1") (pintype "passive"))
      (node (ref "C19") (pin "1") (pinfunction "1_1") (pintype "passive"))
      (node (ref "C25") (pin "1") (pinfunction "1_1") (pintype "passive"))
      (node (ref "C33") (pin "1") (pinfunction "1_1") (pintype "passive"))
      (node (ref "C6") (pin "1") (pinfunction "1_1") (pintype "passive"))
      (node (ref "C7") (pin "1") (pinfunction "1_1") (pintype "passive"))
      (node (ref "C8") (pin "1") (pinfunction "1_1") (pintype "passive"))
      (node (ref "IC3") (pin "10") (pinfunction "CSB_10") (pintype "bidirectional"))
      (node (ref "IC3") (pin "3") (pinfunction "VDDIO_3") (pintype "bidirectional"))
      (node (ref "IC3") (pin "7") (pinfunction "VDD_7") (pintype "bidirectional"))
      (node (ref "IC9") (pin "E2") (pinfunction "VOUT_1_E2") (pintype "bidirectional"))
      (node (ref "IC9") (pin "E3") (pinfunction "VOUT_2_E3") (pintype "bidirectional"))
      (node (ref "J2") (pin "1") (pinfunction "1_1") (pintype "bidirectional"))
      (node (ref "R17") (pin "1") (pinfunction "1_1") (pintype "bidirectional"))
      (node (ref "R18") (pin "1") (pinfunction "1_1") (pintype "bidirectional"))
      (node (ref "TP_3.3V") (pin "TP") (pinfunction "TP_TP") (pintype "input"))
      (node (ref "TP_3V3") (pin "TP") (pinfunction "TP_TP") (pintype "input"))
      (node (ref "U1") (pin "P$A22") (pinfunction "VDD_P$A22") (pintype "power_in"))
      (node (ref "U1") (pin "P$AD14") (pinfunction "VDD_P$AD14") (pintype "power_in"))
      (node (ref "U1") (pin "P$AD23") (pinfunction "VDD_P$AD23") (pintype "power_in"))
      (node (ref "U1") (pin "P$B1") (pinfunction "VDD_P$B1") (pintype "power_in"))
      (node (ref "U1") (pin "P$W1") (pinfunction "VDD_P$W1") (pintype "power_in"))
      (node (ref "U1") (pin "P$Y2") (pinfunction "VDDH_P$Y2") (pintype "power_in"))
    )
    (net (code "6") (name "ALERT{slash}1.6C") (class "Default")
      (node (ref "U3") (pin "5") (pinfunction "~{ALERT}_5") (pintype "output"))
    )
    (net (code "7") (name "D+{slash}1.5D") (class "Default")
      (node (ref "D3") (pin "4") (pinfunction "I/O2_2_4") (pintype "bidirectional"))
    )
    (net (code "8") (name "D+{slash}2.7D") (class "Default")
      (node (ref "U1") (pin "P$AD6") (pinfunction "D+_P$AD6") (pintype "bidirectional"))
    )
    (net (code "9") (name "D-{slash}1.5D") (class "Default")
      (node (ref "D3") (pin "6") (pinfunction "I/O1_2_6") (pintype "bidirectional"))
    )
    (net (code "10") (name "D-{slash}2.7D") (class "Default")
      (node (ref "U1") (pin "P$AD4") (pinfunction "D-_P$AD4") (pintype "bidirectional"))
    )
    (net (code "11") (name "DN") (class "Default")
      (node (ref "D3") (pin "1") (pinfunction "I/O1_1_1") (pintype "bidirectional"))
      (node (ref "J4") (pin "A7") (pinfunction "DN1_A7") (pintype "bidirectional"))
      (node (ref "J4") (pin "B7") (pinfunction "DN2_B7") (pintype "bidirectional"))
    )
    (net (code "12") (name "DP") (class "Default")
      (node (ref "D3") (pin "3") (pinfunction "I/O2_1_3") (pintype "bidirectional"))
      (node (ref "J4") (pin "A6") (pinfunction "DP1_A6") (pintype "bidirectional"))
      (node (ref "J4") (pin "B6") (pinfunction "DP2_B6") (pintype "bidirectional"))
    )
    (net (code "13") (name "EPD_3V3") (class "Default")
      (node (ref "C1-EP-DR") (pin "1") (pinfunction "1_1") (pintype "passive"))
      (node (ref "EPD_C5") (pin "2") (pinfunction "2_2") (pintype "passive"))
      (node (ref "J1") (pin "15") (pinfunction "15_15") (pintype "bidirectional"))
      (node (ref "J1") (pin "16") (pinfunction "16_16") (pintype "bidirectional"))
      (node (ref "L5") (pin "2") (pinfunction "2_2") (pintype "passive"))
      (node (ref "Q1") (pin "3") (pinfunction "D_3") (pintype "bidirectional"))
    )
    (net (code "14") (name "EPD_BUSY{slash}1.5D") (class "Default")
      (node (ref "J1") (pin "9") (pinfunction "9_9") (pintype "bidirectional"))
    )
    (net (code "15") (name "EPD_BUSY{slash}2.2D") (class "Default")
      (node (ref "U1") (pin "P$AD12") (pinfunction "P0.17_P$AD12") (pintype "bidirectional"))
    )
    (net (code "16") (name "EPD_CS{slash}1.4C") (class "Default")
      (node (ref "J1") (pin "12") (pinfunction "12_12") (pintype "bidirectional"))
    )
    (net (code "17") (name "EPD_CS{slash}2.2D") (class "Default")
      (node (ref "U1") (pin "P$K2") (pinfunction "P0.05/AIN3_P$K2") (pintype "bidirectional"))
    )
    (net (code "18") (name "EPD_DC{slash}1.5D") (class "Default")
      (node (ref "J1") (pin "11") (pinfunction "11_11") (pintype "bidirectional"))
    )
    (net (code "19") (name "EPD_DC{slash}2.2D") (class "Default")
      (node (ref "U1") (pin "P$AD10") (pinfunction "P0.15_P$AD10") (pintype "bidirectional"))
    )
    (net (code "20") (name "EPD_RST{slash}1.5D") (class "Default")
      (node (ref "J1") (pin "10") (pinfunction "10_10") (pintype "bidirectional"))
    )
    (net (code "21") (name "EPD_RST{slash}2.2D") (class "Default")
      (node (ref "U1") (pin "P$AC11") (pinfunction "P0.16_P$AC11") (pintype "bidirectional"))
    )
    (net (code "22") (name "GDR") (class "Default")
      (node (ref "J1") (pin "2") (pinfunction "2_2") (pintype "bidirectional"))
      (node (ref "Q3") (pin "1") (pinfunction "G_1") (pintype "bidirectional"))
      (node (ref "R2_EP_DR") (pin "2") (pinfunction "2_2") (pintype "bidirectional"))
    )
    (net (code "23") (name "GND") (class "Default")
      (node (ref "C1") (pin "2") (pinfunction "2_2") (pintype "passive"))
      (node (ref "C1-EP-DR") (pin "2") (pinfunction "2_2") (pintype "passive"))
      (node (ref "C10") (pin "2") (pinfunction "2_2") (pintype "passive"))
      (node (ref "C11") (pin "2") (pinfunction "2_2") (pintype "passive"))
      (node (ref "C12") (pin "2") (pinfunction "2_2") (pintype "passive"))
      (node (ref "C13") (pin "2") (pinfunction "2_2") (pintype "passive"))
      (node (ref "C14") (pin "2") (pinfunction "2_2") (pintype "passive"))
      (node (ref "C15") (pin "2") (pinfunction "2_2") (pintype "passive"))
      (node (ref "C16") (pin "2") (pinfunction "2_2") (pintype "passive"))
      (node (ref "C17") (pin "1") (pinfunction "1_1") (pintype "passive"))
      (node (ref "C18") (pin "1") (pinfunction "1_1") (pintype "passive"))
      (node (ref "C19") (pin "2") (pinfunction "2_2") (pintype "passive"))
      (node (ref "C2") (pin "2") (pinfunction "2_2") (pintype "passive"))
      (node (ref "C20") (pin "2") (pinfunction "2_2") (pintype "passive"))
      (node (ref "C21") (pin "2") (pinfunction "2_2") (pintype "passive"))
      (node (ref "C22") (pin "2") (pinfunction "2_2") (pintype "passive"))
      (node (ref "C23") (pin "1") (pinfunction "1_1") (pintype "passive"))
      (node (ref "C24") (pin "1") (pinfunction "1_1") (pintype "passive"))
      (node (ref "C25") (pin "2") (pinfunction "2_2") (pintype "passive"))
      (node (ref "C27") (pin "1") (pinfunction "1_1") (pintype "passive"))
      (node (ref "C29") (pin "1") (pinfunction "1_1") (pintype "passive"))
      (node (ref "C3") (pin "2") (pinfunction "2_2") (pintype "passive"))
      (node (ref "C30") (pin "1") (pinfunction "1_1") (pintype "passive"))
      (node (ref "C31") (pin "1") (pinfunction "1_1") (pintype "passive"))
      (node (ref "C32") (pin "1") (pinfunction "1_1") (pintype "passive"))
      (node (ref "C33") (pin "2") (pinfunction "2_2") (pintype "passive"))
      (node (ref "C34") (pin "1") (pinfunction "1_1") (pintype "passive"))
      (node (ref "C37") (pin "1") (pinfunction "1_1") (pintype "passive"))
      (node (ref "C38") (pin "1") (pinfunction "1_1") (pintype "passive"))
      (node (ref "C39") (pin "2") (pinfunction "2_2") (pintype "passive"))
      (node (ref "C4") (pin "2") (pinfunction "2_2") (pintype "passive"))
      (node (ref "C42") (pin "2") (pinfunction "2_2") (pintype "passive"))
      (node (ref "C43") (pin "2") (pinfunction "2_2") (pintype "passive"))
      (node (ref "C5") (pin "2") (pinfunction "2_2") (pintype "passive"))
      (node (ref "C6") (pin "2") (pinfunction "2_2") (pintype "passive"))
      (node (ref "C7") (pin "2") (pinfunction "2_2") (pintype "passive"))
      (node (ref "C8") (pin "2") (pinfunction "2_2") (pintype "passive"))
      (node (ref "C9") (pin "2") (pinfunction "2_2") (pintype "passive"))
      (node (ref "D3") (pin "2") (pinfunction "GND_2") (pintype "bidirectional"))
      (node (ref "D4") (pin "1") (pinfunction "K_1") (pintype "bidirectional"))
      (node (ref "EPD_C1") (pin "1") (pinfunction "1_1") (pintype "passive"))
      (node (ref "EPD_C10") (pin "1") (pinfunction "1_1") (pintype "passive"))
      (node (ref "EPD_C11") (pin "1") (pinfunction "1_1") (pintype "passive"))
      (node (ref "EPD_C12") (pin "1") (pinfunction "1_1") (pintype "passive"))
      (node (ref "EPD_C2") (pin "1") (pinfunction "1_1") (pintype "passive"))
      (node (ref "EPD_C5") (pin "1") (pinfunction "1_1") (pintype "passive"))
      (node (ref "EPD_C6") (pin "1") (pinfunction "1_1") (pintype "passive"))
      (node (ref "EPD_C7") (pin "1") (pinfunction "1_1") (pintype "passive"))
      (node (ref "EPD_C8") (pin "1") (pinfunction "1_1") (pintype "passive"))
      (node (ref "EPD_C9") (pin "1") (pinfunction "1_1") (pintype "passive"))
      (node (ref "IC1") (pin "D2") (pinfunction "GND_D2") (pintype "bidirectional"))
      (node (ref "IC2") (pin "B1") (pinfunction "IN/TRIG_B1") (pintype "bidirectional"))
      (node (ref "IC2") (pin "B3") (pinfunction "GND_B3") (pintype "bidirectional"))
      (node (ref "IC3") (pin "8") (pinfunction "GNDIO_8") (pintype "bidirectional"))
      (node (ref "IC3") (pin "9") (pinfunction "GND_9") (pintype "bidirectional"))
      (node (ref "IC9") (pin "B1") (pinfunction "VSEL_B1") (pintype "bidirectional"))
      (node (ref "IC9") (pin "C1") (pinfunction "AGND_C1") (pintype "bidirectional"))
      (node (ref "IC9") (pin "C2") (pinfunction "PGND_1_C2") (pintype "bidirectional"))
      (node (ref "IC9") (pin "C3") (pinfunction "PGND_2_C3") (pintype "bidirectional"))
      (node (ref "J1") (pin "17") (pinfunction "17_17") (pintype "bidirectional"))
      (node (ref "J1") (pin "8") (pinfunction "8_8") (pintype "bidirectional"))
      (node (ref "J1") (pin "MP1") (pinfunction "MP1_MP1") (pintype "bidirectional"))
      (node (ref "J1") (pin "MP2") (pinfunction "MP2_MP2") (pintype "bidirectional"))
      (node (ref "J2") (pin "3") (pinfunction "3_3") (pintype "bidirectional"))
      (node (ref "J2") (pin "5") (pinfunction "5_5") (pintype "bidirectional"))
      (node (ref "J4") (pin "A12_B1") (pinfunction "GND_A12_B1") (pintype "power_in"))
      (node (ref "J4") (pin "A1_B12") (pinfunction "GND_A1_B12") (pintype "power_in"))
      (node (ref "J4") (pin "SH1") (pinfunction "SHIELD_SH1") (pintype "passive"))
      (node (ref "J4") (pin "SH2") (pinfunction "SHIELD_SH2") (pintype "passive"))
      (node (ref "J4") (pin "SH3") (pinfunction "SHIELD_SH3") (pintype "passive"))
      (node (ref "J4") (pin "SH4") (pinfunction "SHIELD_SH4") (pintype "passive"))
      (node (ref "R1_USB") (pin "1") (pinfunction "1_1") (pintype "bidirectional"))
      (node (ref "R2_EP_DR") (pin "1") (pinfunction "1_1") (pintype "bidirectional"))
      (node (ref "R2_USB") (pin "2") (pinfunction "2_2") (pintype "bidirectional"))
      (node (ref "R3") (pin "1") (pinfunction "1_1") (pintype "bidirectional"))
      (node (ref "R9") (pin "1") (pinfunction "1_1") (pintype "bidirectional"))
      (node (ref "R_TYPE_SEL") (pin "1") (pinfunction "1_1") (pintype "bidirectional"))
      (node (ref "SJ1") (pin "1") (pinfunction "1_1") (pintype "passive"))
      (node (ref "SW_DN") (pin "1") (pinfunction "1_1") (pintype "passive"))
      (node (ref "SW_ENT") (pin "1") (pinfunction "1_1") (pintype "passive"))
      (node (ref "SW_UP") (pin "1") (pinfunction "1_1") (pintype "passive"))
      (node (ref "TP_BAT_GND") (pin "TP") (pinfunction "TP_TP") (pintype "input"))
      (node (ref "TP_GND") (pin "TP") (pinfunction "TP_TP") (pintype "input"))
      (node (ref "U1") (pin "P$74") (pinfunction "VSS_PAD_P$74") (pintype "bidirectional"))
      (node (ref "U1") (pin "P$75") (pinfunction "VSS_PAD_P$75") (pintype "bidirectional"))
      (node (ref "U1") (pin "P$76") (pinfunction "VSS_PAD_P$76") (pintype "bidirectional"))
      (node (ref "U1") (pin "P$77") (pinfunction "VSS_PAD_P$77") (pintype "bidirectional"))
      (node (ref "U1") (pin "P$78") (pinfunction "VSS_PAD_P$78") (pintype "bidirectional"))
      (node (ref "U1") (pin "P$79") (pinfunction "VSS_PAD_P$79") (pintype "bidirectional"))
      (node (ref "U1") (pin "P$80") (pinfunction "VSS_PAD_P$80") (pintype "bidirectional"))
      (node (ref "U1") (pin "P$81") (pinfunction "VSS_PAD_P$81") (pintype "bidirectional"))
      (node (ref "U1") (pin "P$82") (pinfunction "VSS_PAD_P$82") (pintype "bidirectional"))
      (node (ref "U1") (pin "P$83") (pinfunction "VSS_PAD_P$83") (pintype "bidirectional"))
      (node (ref "U1") (pin "P$84") (pinfunction "VSS_PAD_P$84") (pintype "bidirectional"))
      (node (ref "U1") (pin "P$85") (pinfunction "VSS_PAD_P$85") (pintype "bidirectional"))
      (node (ref "U1") (pin "P$86") (pinfunction "VSS_PAD_P$86") (pintype "bidirectional"))
      (node (ref "U1") (pin "P$87") (pinfunction "VSS_PAD_P$87") (pintype "bidirectional"))
      (node (ref "U1") (pin "P$88") (pinfunction "VSS_PAD_P$88") (pintype "bidirectional"))
      (node (ref "U1") (pin "P$89") (pinfunction "VSS_PAD_P$89") (pintype "bidirectional"))
      (node (ref "U1") (pin "P$90") (pinfunction "VSS_PAD_P$90") (pintype "bidirectional"))
      (node (ref "U1") (pin "P$B7") (pinfunction "VSS_P$B7") (pintype "power_in"))
      (node (ref "U1") (pin "P$F23") (pinfunction "VSS_PA_P$F23") (pintype "bidirectional"))
      (node (ref "U3") (pin "1") (pinfunction "CTG_1") (pintype "power_in"))
      (node (ref "U3") (pin "4") (pinfunction "GND_4") (pintype "power_in"))
      (node (ref "U3") (pin "6") (pinfunction "QSTRT_6") (pintype "input"))
      (node (ref "U3") (pin "9") (pinfunction "EP_9") (pintype "power_in"))
      (node (ref "X1") (pin "2") (pinfunction "2_2") (pintype "passive"))
      (node (ref "X1") (pin "4") (pinfunction "4_4") (pintype "passive"))
    )
    (net (code "24") (name "HAPTIC_EN{slash}1.4C") (class "Default")
      (node (ref "IC2") (pin "A1") (pinfunction "EN_A1") (pintype "bidirectional"))
    )
    (net (code "25") (name "HAPTIC_EN{slash}2.6A") (class "Default")
      (node (ref "U1") (pin "P$U1") (pinfunction "P0.12_P$U1") (pintype "bidirectional"))
    )
    (net (code "26") (name "IMU_INT1") (class "Default")
      (node (ref "IC3") (pin "5") (pinfunction "INT1_5") (pintype "bidirectional"))
      (node (ref "U1") (pin "P$N1") (pinfunction "P0.08_P$N1") (pintype "bidirectional"))
    )
    (net (code "27") (name "IMU_INT2") (class "Default")
      (node (ref "IC3") (pin "6") (pinfunction "INT2_6") (pintype "bidirectional"))
      (node (ref "U1") (pin "P$P2") (pinfunction "P1.08_P$P2") (pintype "bidirectional"))
    )
    (net (code "28") (name "LX1") (class "Default")
      (node (ref "IC9") (pin "B2") (pinfunction "SW1_1_B2") (pintype "bidirectional"))
      (node (ref "IC9") (pin "B3") (pinfunction "SW1_2_B3") (pintype "bidirectional"))
      (node (ref "L7") (pin "1") (pinfunction "1_1") (pintype "bidirectional"))
    )
    (net (code "29") (name "LX2") (class "Default")
      (node (ref "IC9") (pin "D2") (pinfunction "SW2_1_D2") (pintype "bidirectional"))
      (node (ref "IC9") (pin "D3") (pinfunction "SW2_2_D3") (pintype "bidirectional"))
      (node (ref "L7") (pin "2") (pinfunction "2_2") (pintype "bidirectional"))
    )
    (net (code "30") (name "MOSI{slash}1.5B") (class "Default")
      (node (ref "J1") (pin "14") (pinfunction "14_14") (pintype "bidirectional"))
    )
    (net (code "31") (name "MOSI{slash}2.2D") (class "Default")
      (node (ref "U1") (pin "P$B13") (pinfunction "P0.03/AIN1_P$B13") (pintype "bidirectional"))
    )
    (net (code "32") (name "N$12") (class "Default")
      (node (ref "U1") (pin "P$J24") (pinfunction "P0.10/NFC2_P$J24") (pintype "bidirectional"))
    )
    (net (code "33") (name "N$13") (class "Default")
      (node (ref "U1") (pin "P$L24") (pinfunction "P0.09/NFC1_P$L24") (pintype "bidirectional"))
    )
    (net (code "34") (name "Net-(ANT1-FEED)") (class "Default")
      (node (ref "ANT1") (pin "1") (pinfunction "FEED_1") (pintype "input"))
      (node (ref "C22") (pin "1") (pinfunction "1_1") (pintype "passive"))
      (node (ref "C4") (pin "1") (pinfunction "1_1") (pintype "passive"))
      (node (ref "L1") (pin "2") (pinfunction "2_2") (pintype "passive"))
    )
    (net (code "35") (name "Net-(D2-K)") (class "Default")
      (node (ref "C2-EP-DR") (pin "1") (pinfunction "1_1") (pintype "passive"))
      (node (ref "D2") (pin "1") (pinfunction "K_1") (pintype "bidirectional"))
      (node (ref "D4") (pin "2") (pinfunction "A_2") (pintype "bidirectional"))
    )
    (net (code "36") (name "Net-(D5-A)") (class "Default")
      (node (ref "C2-EP-DR") (pin "2") (pinfunction "2_2") (pintype "passive"))
      (node (ref "D5") (pin "2") (pinfunction "A_2") (pintype "bidirectional"))
      (node (ref "L5") (pin "1") (pinfunction "1_1") (pintype "passive"))
      (node (ref "Q3") (pin "3") (pinfunction "D_3") (pintype "bidirectional"))
    )
    (net (code "37") (name "Net-(EPD_C1-Pad2)") (class "Default")
      (node (ref "EPD_C1") (pin "2") (pinfunction "2_2") (pintype "passive"))
      (node (ref "J1") (pin "5") (pinfunction "5_5") (pintype "bidirectional"))
    )
    (net (code "38") (name "Net-(EPD_C2-Pad2)") (class "Default")
      (node (ref "EPD_C2") (pin "2") (pinfunction "2_2") (pintype "passive"))
      (node (ref "J1") (pin "4") (pinfunction "4_4") (pintype "bidirectional"))
    )
    (net (code "39") (name "Net-(EPD_C6-Pad2)") (class "Default")
      (node (ref "EPD_C6") (pin "2") (pinfunction "2_2") (pintype "passive"))
      (node (ref "J1") (pin "18") (pinfunction "18_18") (pintype "bidirectional"))
    )
    (net (code "40") (name "Net-(EPD_C7-Pad2)") (class "Default")
      (node (ref "EPD_C7") (pin "2") (pinfunction "2_2") (pintype "passive"))
      (node (ref "J1") (pin "19") (pinfunction "19_19") (pintype "bidirectional"))
    )
    (net (code "41") (name "Net-(EPD_C8-Pad2)") (class "Default")
      (node (ref "EPD_C8") (pin "2") (pinfunction "2_2") (pintype "passive"))
      (node (ref "J1") (pin "20") (pinfunction "20_20") (pintype "bidirectional"))
    )
    (net (code "42") (name "Net-(EPD_C10-Pad2)") (class "Default")
      (node (ref "EPD_C10") (pin "2") (pinfunction "2_2") (pintype "passive"))
      (node (ref "J1") (pin "22") (pinfunction "22_22") (pintype "bidirectional"))
    )
    (net (code "43") (name "Net-(EPD_C12-Pad2)") (class "Default")
      (node (ref "EPD_C12") (pin "2") (pinfunction "2_2") (pintype "passive"))
      (node (ref "J1") (pin "24") (pinfunction "24_24") (pintype "bidirectional"))
    )
    (net (code "44") (name "Net-(IC1-TS{slash}MR)") (class "Default")
      (node (ref "IC1") (pin "D1") (pinfunction "TS/MR_D1") (pintype "bidirectional"))
      (node (ref "R9") (pin "2") (pinfunction "2_2") (pintype "bidirectional"))
    )
    (net (code "45") (name "Net-(IC2-REG)") (class "Default")
      (node (ref "C32") (pin "2") (pinfunction "2_2") (pintype "passive"))
      (node (ref "IC2") (pin "A2") (pinfunction "REG_A2") (pintype "bidirectional"))
    )
    (net (code "46") (name "Net-(IC3-SDO)") (class "Default")
      (node (ref "IC3") (pin "1") (pinfunction "SDO_1") (pintype "bidirectional"))
      (node (ref "R3") (pin "2") (pinfunction "2_2") (pintype "bidirectional"))
    )
    (net (code "47") (name "Net-(IC9-SCL)") (class "Default")
      (node (ref "IC9") (pin "D1") (pinfunction "SCL_D1") (pintype "bidirectional"))
      (node (ref "R4") (pin "2") (pinfunction "2_2") (pintype "bidirectional"))
    )
    (net (code "48") (name "Net-(IC9-SDA)") (class "Default")
      (node (ref "IC9") (pin "E1") (pinfunction "SDA_E1") (pintype "bidirectional"))
      (node (ref "R2") (pin "2") (pinfunction "2_2") (pintype "bidirectional"))
    )
    (net (code "49") (name "Net-(J4-CC1)") (class "Default")
      (node (ref "J4") (pin "A5") (pinfunction "CC1_A5") (pintype "bidirectional"))
      (node (ref "R1_USB") (pin "2") (pinfunction "2_2") (pintype "bidirectional"))
    )
    (net (code "50") (name "Net-(J4-CC2)") (class "Default")
      (node (ref "J4") (pin "B5") (pinfunction "CC2_B5") (pintype "bidirectional"))
      (node (ref "R2_USB") (pin "1") (pinfunction "1_1") (pintype "bidirectional"))
    )
    (net (code "51") (name "Net-(L2-Pad2)") (class "Default")
      (node (ref "L2") (pin "2") (pinfunction "2_2") (pintype "passive"))
      (node (ref "L3") (pin "1") (pinfunction "1_1") (pintype "passive"))
    )
    (net (code "52") (name "Net-(R1_EP_DR-Pad1)") (class "Default")
      (node (ref "R1_EP_DR") (pin "1") (pinfunction "1_1") (pintype "bidirectional"))
      (node (ref "R_TYPE_SEL") (pin "2") (pinfunction "2_2") (pintype "bidirectional"))
      (node (ref "SJ1") (pin "2") (pinfunction "2_2") (pintype "passive"))
    )
    (net (code "53") (name "Net-(U1-ANT)") (class "Default")
      (node (ref "C3") (pin "1") (pinfunction "1_1") (pintype "passive"))
      (node (ref "L1") (pin "1") (pinfunction "1_1") (pintype "passive"))
      (node (ref "U1") (pin "P$H23") (pinfunction "ANT_P$H23") (pintype "bidirectional"))
    )
    (net (code "54") (name "Net-(U1-DCC)") (class "Default")
      (node (ref "L2") (pin "1") (pinfunction "1_1") (pintype "passive"))
      (node (ref "U1") (pin "P$B3") (pinfunction "DCC_P$B3") (pintype "output"))
    )
    (net (code "55") (name "Net-(U1-DEC2)") (class "Default")
      (node (ref "C13") (pin "1") (pinfunction "1_1") (pintype "passive"))
      (node (ref "U1") (pin "P$A18") (pinfunction "DEC2_P$A18") (pintype "bidirectional"))
    )
    (net (code "56") (name "Net-(U1-DEC3V3)") (class "Default")
      (node (ref "C20") (pin "1") (pinfunction "1_1") (pintype "passive"))
      (node (ref "U1") (pin "P$AC5") (pinfunction "DEC3V3_P$AC5") (pintype "bidirectional"))
    )
    (net (code "57") (name "Net-(U1-DEC5)") (class "Default")
      (node (ref "C9") (pin "1") (pinfunction "1_1") (pintype "passive"))
      (node (ref "U1") (pin "P$N24") (pinfunction "DEC5_P$N24") (pintype "bidirectional"))
    )
    (net (code "58") (name "Net-(U1-P0.00{slash}XL1)") (class "Default")
      (node (ref "C17") (pin "2") (pinfunction "2_2") (pintype "passive"))
      (node (ref "U1") (pin "P$D2") (pinfunction "P0.00/XL1_P$D2") (pintype "bidirectional"))
      (node (ref "X2") (pin "1") (pinfunction "1_1") (pintype "passive"))
    )
    (net (code "59") (name "Net-(U1-P0.01{slash}XL2)") (class "Default")
      (node (ref "C18") (pin "2") (pinfunction "2_2") (pintype "passive"))
      (node (ref "U1") (pin "P$F2") (pinfunction "P0.01/XL2_P$F2") (pintype "bidirectional"))
      (node (ref "X2") (pin "2") (pinfunction "2_2") (pintype "passive"))
    )
    (net (code "60") (name "Net-(U1-XC1)") (class "Default")
      (node (ref "C1") (pin "1") (pinfunction "1_1") (pintype "passive"))
      (node (ref "U1") (pin "P$B24") (pinfunction "XC1_P$B24") (pintype "input"))
      (node (ref "X1") (pin "1") (pinfunction "1_1") (pintype "passive"))
    )
    (net (code "61") (name "Net-(U1-XC2)") (class "Default")
      (node (ref "C2") (pin "1") (pinfunction "1_1") (pintype "passive"))
      (node (ref "U1") (pin "P$A23") (pinfunction "XC2_P$A23") (pintype "output"))
      (node (ref "X1") (pin "3") (pinfunction "3_3") (pintype "passive"))
    )
    (net (code "62") (name "OUT+") (class "Default")
      (node (ref "IC2") (pin "A3") (pinfunction "OUT+_A3") (pintype "bidirectional"))
      (node (ref "TP_OP") (pin "TP") (pinfunction "TP_TP") (pintype "input"))
    )
    (net (code "63") (name "OUT-") (class "Default")
      (node (ref "IC2") (pin "C3") (pinfunction "OUT-_C3") (pintype "bidirectional"))
      (node (ref "TP_ON") (pin "TP") (pinfunction "TP_TP") (pintype "input"))
    )
    (net (code "64") (name "P0.04") (class "Default")
      (node (ref "U1") (pin "P$J1") (pinfunction "P0.04/AIN2_P$J1") (pintype "bidirectional"))
    )
    (net (code "65") (name "P0.13{slash}1.5D") (class "Default")
      (node (ref "C30") (pin "2") (pinfunction "2_2") (pintype "passive"))
      (node (ref "R5") (pin "1") (pinfunction "1_1") (pintype "bidirectional"))
      (node (ref "SW_UP") (pin "2") (pinfunction "2_2") (pintype "passive"))
    )
    (net (code "66") (name "P0.13{slash}2.6C") (class "Default")
      (node (ref "U1") (pin "P$AD8") (pinfunction "P0.13_P$AD8") (pintype "bidirectional"))
    )
    (net (code "67") (name "P0.14{slash}1.5D") (class "Default")
      (node (ref "C31") (pin "2") (pinfunction "2_2") (pintype "passive"))
      (node (ref "R8") (pin "1") (pinfunction "1_1") (pintype "bidirectional"))
      (node (ref "SW_ENT") (pin "2") (pinfunction "2_2") (pintype "passive"))
    )
    (net (code "68") (name "P0.14{slash}2.7C") (class "Default")
      (node (ref "U1") (pin "P$AC9") (pinfunction "P0.14_P$AC9") (pintype "bidirectional"))
    )
    (net (code "69") (name "P0.19") (class "Default")
      (node (ref "U1") (pin "P$AC15") (pinfunction "P0.19_P$AC15") (pintype "bidirectional"))
    )
    (net (code "70") (name "P0.20") (class "Default")
      (node (ref "U1") (pin "P$AD16") (pinfunction "P0.20_P$AD16") (pintype "bidirectional"))
    )
    (net (code "71") (name "P0.21") (class "Default")
      (node (ref "U1") (pin "P$AC17") (pinfunction "P0.21_P$AC17") (pintype "bidirectional"))
    )
    (net (code "72") (name "P0.22") (class "Default")
      (node (ref "U1") (pin "P$AD18") (pinfunction "P0.22_P$AD18") (pintype "bidirectional"))
    )
    (net (code "73") (name "P0.23") (class "Default")
      (node (ref "U1") (pin "P$AC19") (pinfunction "P0.23_P$AC19") (pintype "bidirectional"))
    )
    (net (code "74") (name "P0.24") (class "Default")
      (node (ref "U1") (pin "P$AD20") (pinfunction "P0.24_P$AD20") (pintype "bidirectional"))
    )
    (net (code "75") (name "P0.25") (class "Default")
      (node (ref "U1") (pin "P$AC21") (pinfunction "P0.25_P$AC21") (pintype "bidirectional"))
    )
    (net (code "76") (name "P0.26") (class "Default")
      (node (ref "U1") (pin "P$G1") (pinfunction "P0.26_P$G1") (pintype "bidirectional"))
    )
    (net (code "77") (name "P0.27") (class "Default")
      (node (ref "U1") (pin "P$H2") (pinfunction "P0.27_P$H2") (pintype "bidirectional"))
    )
    (net (code "78") (name "P0.28") (class "Default")
      (node (ref "U1") (pin "P$B11") (pinfunction "P0.28/AIN4_P$B11") (pintype "bidirectional"))
    )
    (net (code "79") (name "P0.29") (class "Default")
      (node (ref "U1") (pin "P$A10") (pinfunction "P0.29/AIN5_P$A10") (pintype "bidirectional"))
    )
    (net (code "80") (name "P0.30") (class "Default")
      (node (ref "U1") (pin "P$B9") (pinfunction "P0.30/AIN6_P$B9") (pintype "bidirectional"))
    )
    (net (code "81") (name "P0.31") (class "Default")
      (node (ref "U1") (pin "P$A8") (pinfunction "P0.31/AIN7_P$A8") (pintype "bidirectional"))
    )
    (net (code "82") (name "P1.01{slash}1.6C") (class "Default")
      (node (ref "Q1") (pin "1") (pinfunction "G_1") (pintype "bidirectional"))
      (node (ref "R_PWR_EPD") (pin "1") (pinfunction "1_1") (pintype "bidirectional"))
    )
    (net (code "83") (name "P1.01{slash}2.4B") (class "Default")
      (node (ref "U1") (pin "P$Y23") (pinfunction "P1.01_P$Y23") (pintype "bidirectional"))
    )
    (net (code "84") (name "P1.02{slash}1.6C") (class "Default")
      (node (ref "C29") (pin "2") (pinfunction "2_2") (pintype "passive"))
      (node (ref "R7") (pin "1") (pinfunction "1_1") (pintype "bidirectional"))
      (node (ref "SW_DN") (pin "2") (pinfunction "2_2") (pintype "passive"))
    )
    (net (code "85") (name "P1.02{slash}2.8C") (class "Default")
      (node (ref "U1") (pin "P$W24") (pinfunction "P1.02_P$W24") (pintype "bidirectional"))
    )
    (net (code "86") (name "P1.03") (class "Default")
      (node (ref "U1") (pin "P$V23") (pinfunction "P1.03_P$V23") (pintype "bidirectional"))
    )
    (net (code "87") (name "P1.04") (class "Default")
      (node (ref "U1") (pin "P$U24") (pinfunction "P1.04_P$U24") (pintype "bidirectional"))
    )
    (net (code "88") (name "P1.05") (class "Default")
      (node (ref "U1") (pin "P$T23") (pinfunction "P1.05_P$T23") (pintype "bidirectional"))
    )
    (net (code "89") (name "P1.06") (class "Default")
      (node (ref "U1") (pin "P$R24") (pinfunction "P1.06_P$R24") (pintype "bidirectional"))
    )
    (net (code "90") (name "P1.07") (class "Default")
      (node (ref "U1") (pin "P$P23") (pinfunction "P1.07_P$P23") (pintype "bidirectional"))
    )
    (net (code "91") (name "P1.09") (class "Default")
      (node (ref "U1") (pin "P$R1") (pinfunction "P1.09_P$R1") (pintype "bidirectional"))
    )
    (net (code "92") (name "P1.10") (class "Default")
      (node (ref "U1") (pin "P$A20") (pinfunction "P1.10_P$A20") (pintype "bidirectional"))
    )
    (net (code "93") (name "P1.11") (class "Default")
      (node (ref "U1") (pin "P$B19") (pinfunction "P1.11_P$B19") (pintype "bidirectional"))
    )
    (net (code "94") (name "P1.12") (class "Default")
      (node (ref "U1") (pin "P$B17") (pinfunction "P1.12_P$B17") (pintype "bidirectional"))
    )
    (net (code "95") (name "P1.13") (class "Default")
      (node (ref "U1") (pin "P$A16") (pinfunction "P1.13_P$A16") (pintype "bidirectional"))
    )
    (net (code "96") (name "P1.14") (class "Default")
      (node (ref "U1") (pin "P$B15") (pinfunction "P1.14_P$B15") (pintype "bidirectional"))
    )
    (net (code "97") (name "P1.15") (class "Default")
      (node (ref "U1") (pin "P$A14") (pinfunction "P1.15_P$A14") (pintype "bidirectional"))
    )
    (net (code "98") (name "PMIC_INT") (class "Default")
      (node (ref "IC1") (pin "A1") (pinfunction "~{INT}_A1") (pintype "bidirectional"))
      (node (ref "U1") (pin "P$T2") (pinfunction "P0.11_P$T2") (pintype "bidirectional"))
    )
    (net (code "99") (name "PREVGH") (class "Default")
      (node (ref "D5") (pin "1") (pinfunction "K_1") (pintype "bidirectional"))
      (node (ref "EPD_C9") (pin "2") (pinfunction "2_2") (pintype "passive"))
      (node (ref "J1") (pin "21") (pinfunction "21_21") (pintype "bidirectional"))
    )
    (net (code "100") (name "PREVGL") (class "Default")
      (node (ref "D2") (pin "2") (pinfunction "A_2") (pintype "bidirectional"))
      (node (ref "EPD_C11") (pin "2") (pinfunction "2_2") (pintype "passive"))
      (node (ref "J1") (pin "23") (pinfunction "23_23") (pintype "bidirectional"))
    )
    (net (code "101") (name "RESE") (class "Default")
      (node (ref "J1") (pin "3") (pinfunction "3_3") (pintype "bidirectional"))
      (node (ref "Q3") (pin "2") (pinfunction "S_2") (pintype "bidirectional"))
      (node (ref "R1_EP_DR") (pin "2") (pinfunction "2_2") (pintype "bidirectional"))
    )
    (net (code "102") (name "RESET") (class "Default")
      (node (ref "J2") (pin "6") (pinfunction "6_6") (pintype "bidirectional"))
      (node (ref "TP_RESET") (pin "TP") (pinfunction "TP_TP") (pintype "input"))
      (node (ref "U1") (pin "P$AC13") (pinfunction "P0.18/RESET_P$AC13") (pintype "bidirectional"))
    )
    (net (code "103") (name "SCK{slash}1.5B") (class "Default")
      (node (ref "J1") (pin "13") (pinfunction "13_13") (pintype "bidirectional"))
    )
    (net (code "104") (name "SCK{slash}2.2D") (class "Default")
      (node (ref "U1") (pin "P$A12") (pinfunction "P0.02/AIN0_P$A12") (pintype "bidirectional"))
    )
    (net (code "105") (name "SCL{slash}1.4C") (class "Default")
      (node (ref "IC2") (pin "C1") (pinfunction "SCL_C1") (pintype "bidirectional"))
    )
    (net (code "106") (name "SCL{slash}2.4C") (class "Default")
      (node (ref "IC1") (pin "B1") (pinfunction "SCL_B1") (pintype "bidirectional"))
      (node (ref "IC3") (pin "12") (pinfunction "SCX_12") (pintype "bidirectional"))
      (node (ref "R17") (pin "2") (pinfunction "2_2") (pintype "bidirectional"))
      (node (ref "R4") (pin "1") (pinfunction "1_1") (pintype "bidirectional"))
      (node (ref "TP_SCL") (pin "TP") (pinfunction "TP_TP") (pintype "input"))
      (node (ref "U1") (pin "P$M2") (pinfunction "P0.07_P$M2") (pintype "bidirectional"))
      (node (ref "U3") (pin "7") (pinfunction "SCL_7") (pintype "input"))
    )
    (net (code "107") (name "SDA{slash}1.4C") (class "Default")
      (node (ref "IC2") (pin "B2") (pinfunction "SDA_B2") (pintype "bidirectional"))
      (node (ref "U3") (pin "8") (pinfunction "SDA_8") (pintype "bidirectional"))
    )
    (net (code "108") (name "SDA{slash}2.4C") (class "Default")
      (node (ref "IC1") (pin "C1") (pinfunction "SDA_C1") (pintype "bidirectional"))
      (node (ref "IC3") (pin "2") (pinfunction "SDX_2") (pintype "bidirectional"))
      (node (ref "R18") (pin "2") (pinfunction "2_2") (pintype "bidirectional"))
      (node (ref "R2") (pin "1") (pinfunction "1_1") (pintype "bidirectional"))
      (node (ref "TP_SDA") (pin "TP") (pinfunction "TP_TP") (pintype "input"))
      (node (ref "U1") (pin "P$L1") (pinfunction "P0.06_P$L1") (pintype "bidirectional"))
    )
    (net (code "109") (name "SWDCLK") (class "Default")
      (node (ref "J2") (pin "4") (pinfunction "4_4") (pintype "bidirectional"))
      (node (ref "TP_SWDCLK") (pin "TP") (pinfunction "TP_TP") (pintype "input"))
      (node (ref "U1") (pin "P$AA24") (pinfunction "SWDCLK_P$AA24") (pintype "input"))
    )
    (net (code "110") (name "SWDIO") (class "Default")
      (node (ref "J2") (pin "2") (pinfunction "2_2") (pintype "bidirectional"))
      (node (ref "TP_SWDIO") (pin "TP") (pinfunction "TP_TP") (pintype "input"))
      (node (ref "U1") (pin "P$AC24") (pinfunction "SWDIO_P$AC24") (pintype "bidirectional"))
    )
    (net (code "111") (name "SWO") (class "Default")
      (node (ref "TP_SWO") (pin "TP") (pinfunction "TP_TP") (pintype "input"))
      (node (ref "U1") (pin "P$AD22") (pinfunction "P1.00_P$AD22") (pintype "bidirectional"))
    )
    (net (code "112") (name "VBAT{slash}1.2A") (class "Default")
      (node (ref "C27") (pin "2") (pinfunction "2_2") (pintype "passive"))
      (node (ref "TP_VBAT") (pin "TP") (pinfunction "TP_TP") (pintype "input"))
      (node (ref "U3") (pin "2") (pinfunction "CELL_2") (pintype "power_in"))
      (node (ref "U3") (pin "3") (pinfunction "VDD_3") (pintype "power_in"))
    )
    (net (code "113") (name "VBAT{slash}2.5C") (class "Default")
      (node (ref "C37") (pin "2") (pinfunction "2_2") (pintype "passive"))
      (node (ref "IC1") (pin "C2") (pinfunction "BAT_C2") (pintype "bidirectional"))
    )
    (net (code "114") (name "VBUS{slash}1.5D") (class "Default")
      (node (ref "C42") (pin "1") (pinfunction "1_1") (pintype "passive"))
      (node (ref "C43") (pin "1") (pinfunction "1_1") (pintype "passive"))
      (node (ref "D3") (pin "5") (pinfunction "VBUS_5") (pintype "bidirectional"))
      (node (ref "J4") (pin "A4_B9") (pinfunction "VBUS_A4_B9") (pintype "power_in"))
      (node (ref "J4") (pin "A9_B4") (pinfunction "VBUS_A9_B4") (pintype "power_in"))
    )
    (net (code "115") (name "VBUS{slash}2.6D") (class "Default")
      (node (ref "C21") (pin "1") (pinfunction "1_1") (pintype "passive"))
      (node (ref "C38") (pin "2") (pinfunction "2_2") (pintype "passive"))
      (node (ref "IC1") (pin "A2") (pinfunction "IN_A2") (pintype "bidirectional"))
      (node (ref "U1") (pin "P$AD2") (pinfunction "VBUS_P$AD2") (pintype "power_in"))
    )
    (net (code "116") (name "VREG") (class "Default")
      (node (ref "C23") (pin "2") (pinfunction "2_2") (pintype "passive"))
      (node (ref "C24") (pin "2") (pinfunction "2_2") (pintype "passive"))
      (node (ref "C39") (pin "1") (pinfunction "1_1") (pintype "passive"))
      (node (ref "IC1") (pin "B2") (pinfunction "SYS_B2") (pintype "bidirectional"))
      (node (ref "IC9") (pin "A1") (pinfunction "EN_A1") (pintype "bidirectional"))
      (node (ref "IC9") (pin "A2") (pinfunction "VIN_1_A2") (pintype "bidirectional"))
      (node (ref "IC9") (pin "A3") (pinfunction "VIN_2_A3") (pintype "bidirectional"))
      (node (ref "TP_VREG") (pin "TP") (pinfunction "TP_TP") (pintype "input"))
    )
    (net (code "117") (name "unconnected-(ANT1-NC-Pad2)") (class "Default")
      (node (ref "ANT1") (pin "2") (pinfunction "NC_2") (pintype "no_connect"))
    )
    (net (code "118") (name "unconnected-(IC3-ASCL-Pad11)") (class "Default")
      (node (ref "IC3") (pin "11") (pinfunction "ASCL_11") (pintype "bidirectional"))
    )
    (net (code "119") (name "unconnected-(IC3-ASDA-Pad4)") (class "Default")
      (node (ref "IC3") (pin "4") (pinfunction "ASDA_4") (pintype "bidirectional"))
    )
    (net (code "120") (name "unconnected-(J1-Pad1)") (class "Default")
      (node (ref "J1") (pin "1") (pinfunction "1_1") (pintype "bidirectional"))
    )
    (net (code "121") (name "unconnected-(J1-Pad6)") (class "Default")
      (node (ref "J1") (pin "6") (pinfunction "6_6") (pintype "bidirectional"))
    )
    (net (code "122") (name "unconnected-(J1-Pad7)") (class "Default")
      (node (ref "J1") (pin "7") (pinfunction "7_7") (pintype "bidirectional"))
    )
    (net (code "123") (name "unconnected-(J4-SBU1-PadA8)") (class "Default")
      (node (ref "J4") (pin "A8") (pinfunction "SBU1_A8") (pintype "bidirectional"))
    )
    (net (code "124") (name "unconnected-(J4-SBU2-PadB8)") (class "Default")
      (node (ref "J4") (pin "B8") (pinfunction "SBU2_B8") (pintype "bidirectional"))
    )
    (net (code "125") (name "unconnected-(R_PWR_EPD-Pad2)") (class "Default")
      (node (ref "R_PWR_EPD") (pin "2") (pinfunction "2_2") (pintype "bidirectional"))
    )
    (net (code "126") (name "unconnected-(U1-DCCH-PadP$AB2)") (class "Default")
      (node (ref "U1") (pin "P$AB2") (pinfunction "DCCH_P$AB2") (pintype "bidirectional"))
    )
  )
)
